# Main_board.net
KiCad netlist of a schematic drawn in EAGLE
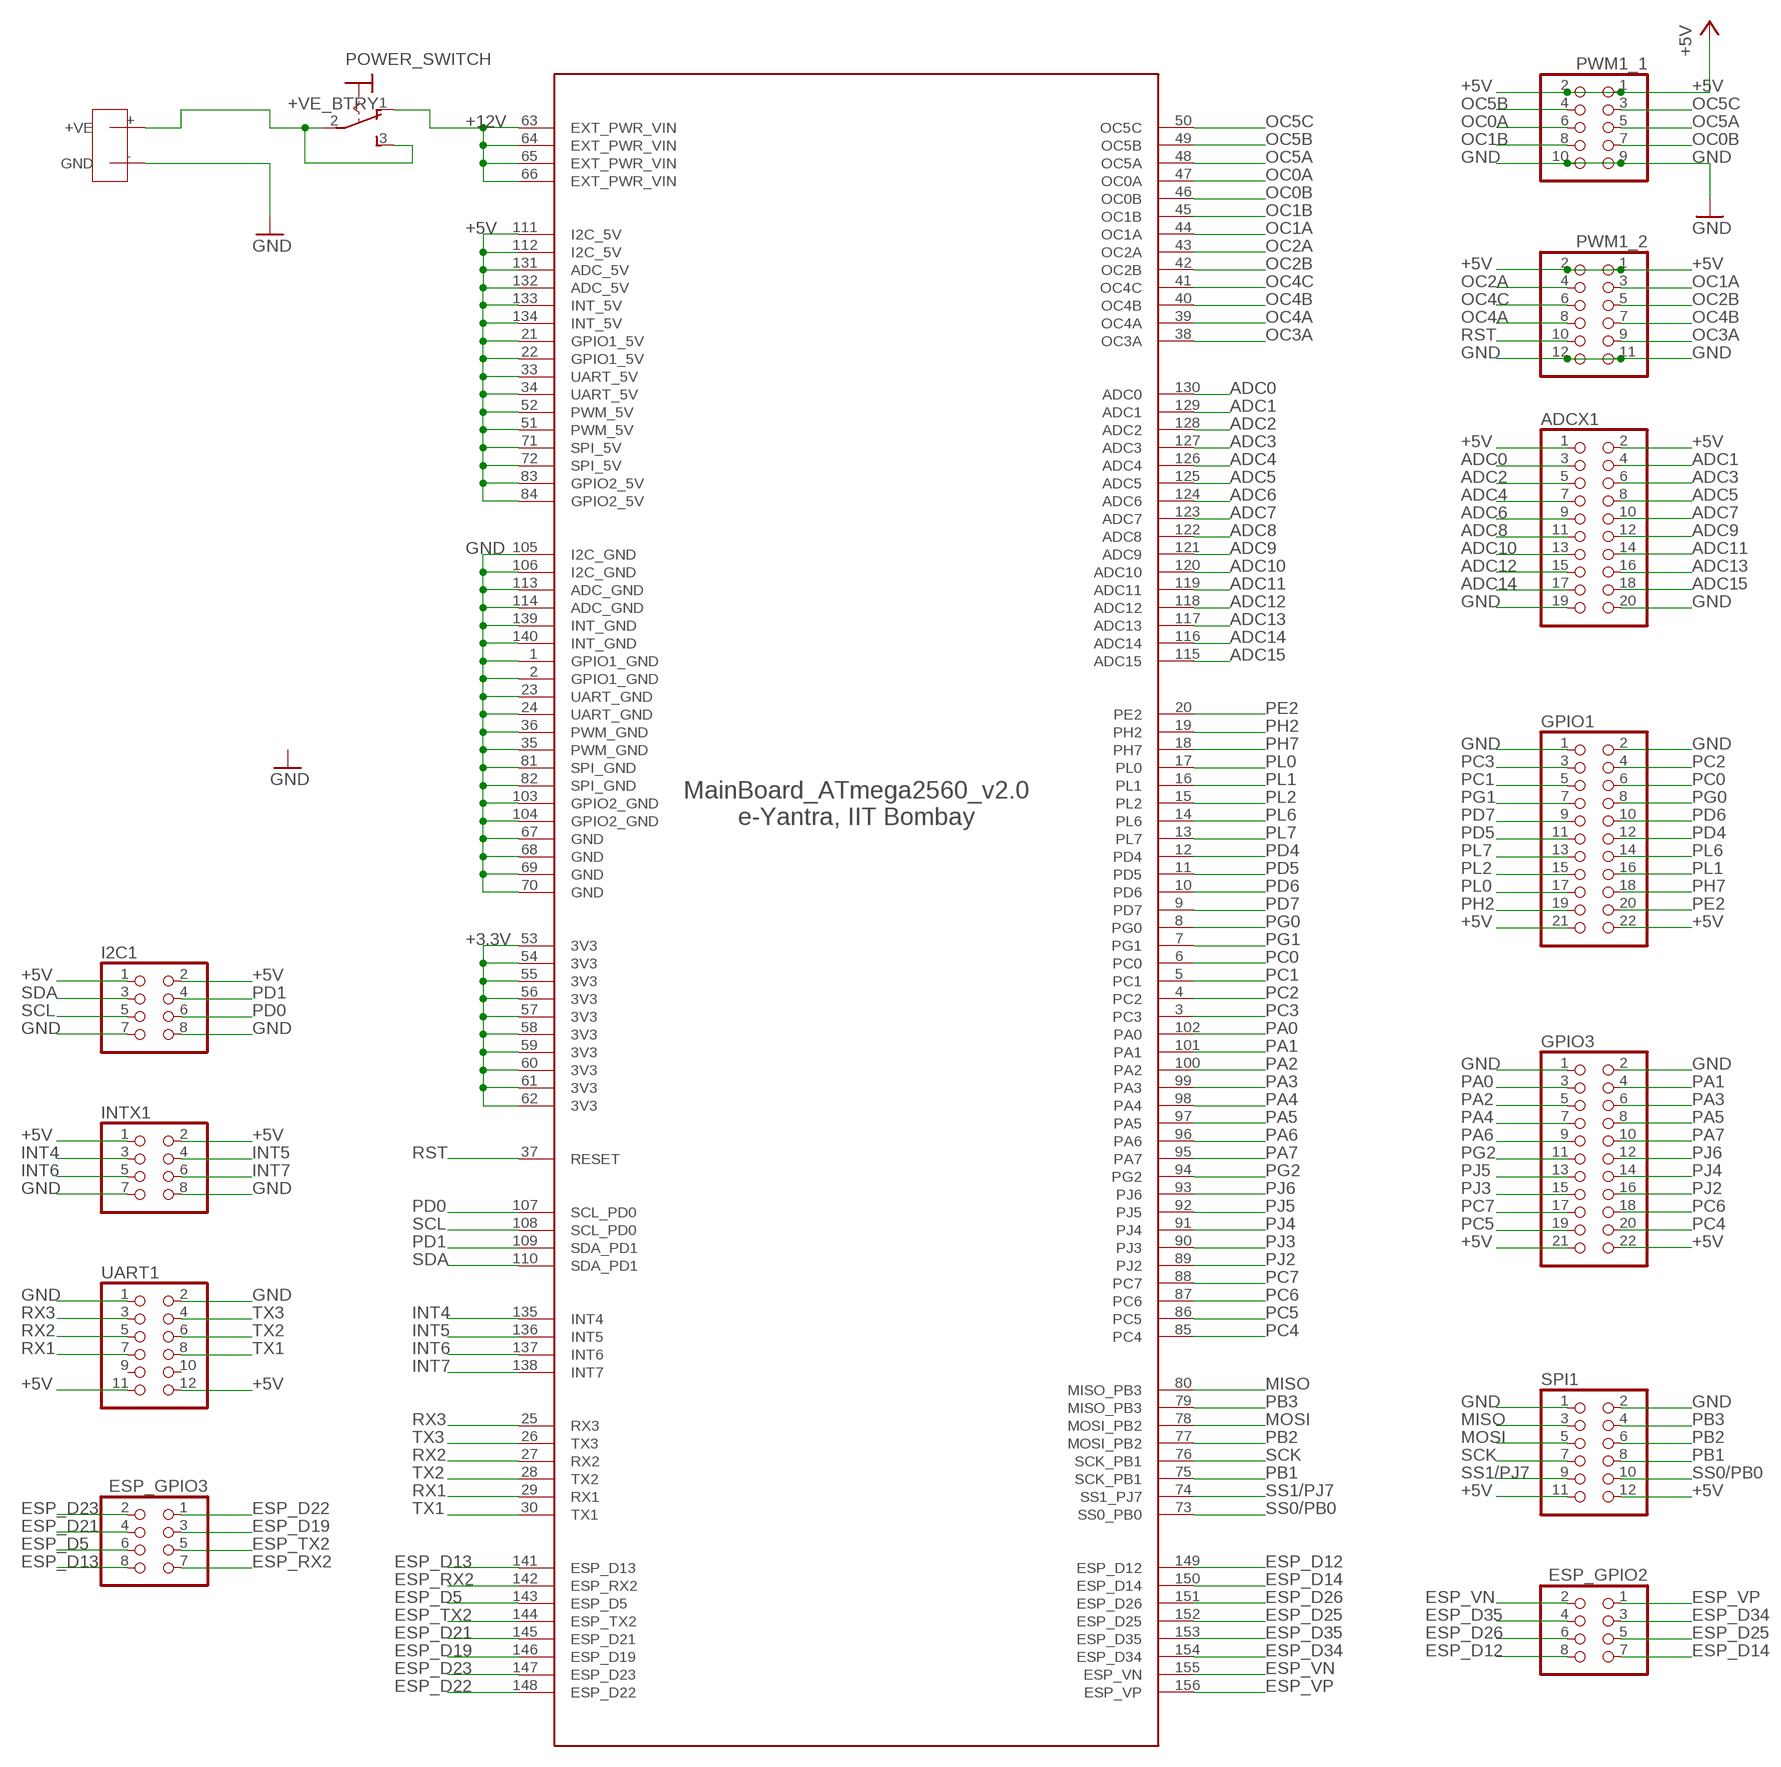
[diagram p0: schematic, sheet 1]
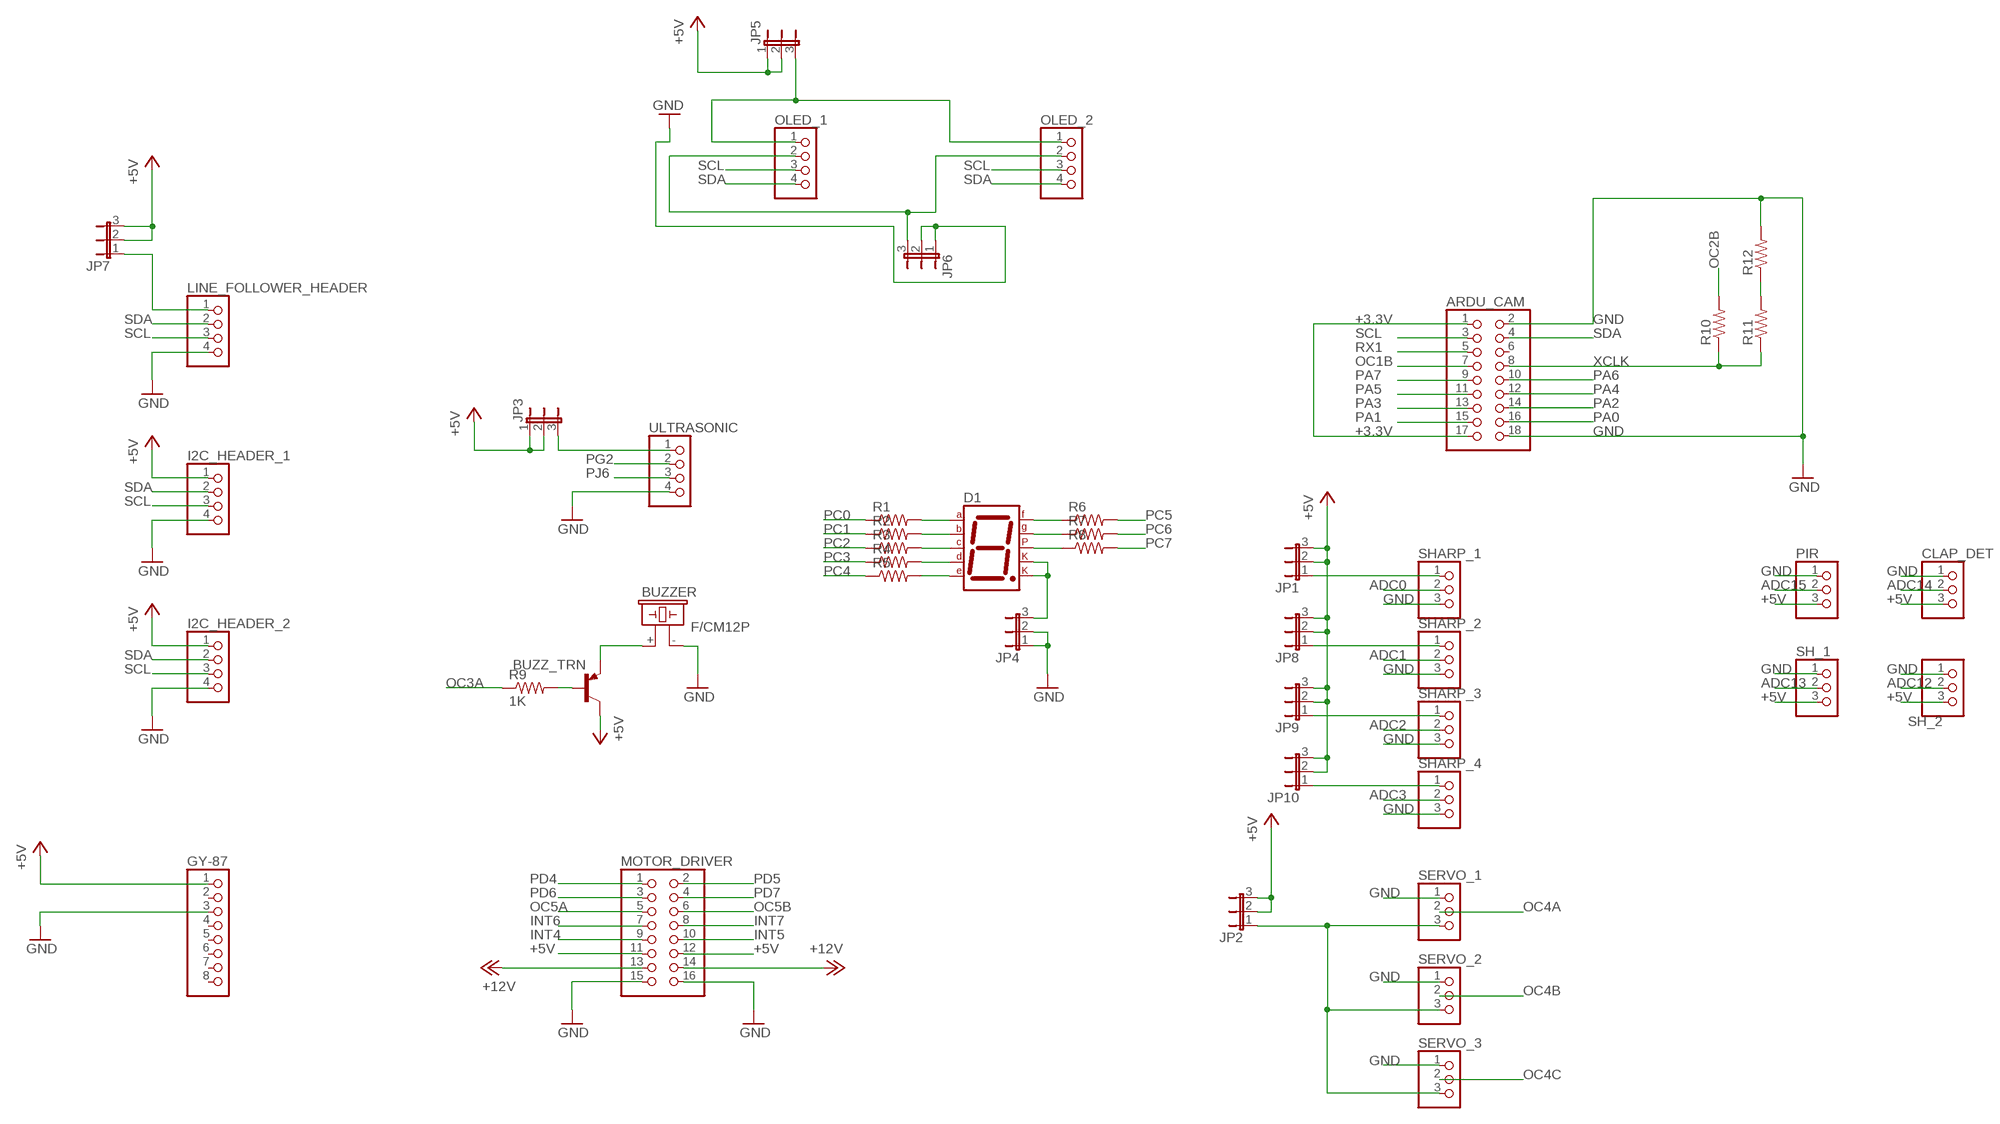
[diagram p1: schematic, sheet 2]

(export (version "E")
  (design (tool "Eeschema 10.0.6"))
  (components
    (comp (ref "ARDU_CAM")
      (value "PINHD-2X9")
      (footprint "eagle-import:2X09")
      (libsource (lib "eagle-import") (part "PINHD-2X9"))
    )
    (comp (ref "BUZZER")
      (value "F/CM12P")
      (footprint "eagle-import:F_CM12P")
      (libsource (lib "eagle-import") (part "F/CM12P"))
    )
    (comp (ref "BUZZ_TRN")
      (value "BC807-16-PNP-SOT23-BEC")
      (footprint "eagle-import:SOT23-BEC")
      (libsource (lib "eagle-import") (part "-PNP-SOT23-BECBC807-16"))
    )
    (comp (ref "CLAP_DET")
      (value "PINHD-1X3")
      (footprint "eagle-import:1X03")
      (libsource (lib "eagle-import") (part "pinhead_325_PINHD-1X3"))
    )
    (comp (ref "D1")
      (value "7SEG-CK")
      (footprint "eagle-import:7SEG-13")
      (libsource (lib "eagle-import") (part "7SEG-CK"))
    )
    (comp (ref "GY-87")
      (value "PINHD-1X8")
      (footprint "eagle-import:1X08")
      (libsource (lib "eagle-import") (part "PINHD-1X8"))
    )
    (comp (ref "I2C_HEADER_1")
      (value "PINHD-1X4")
      (footprint "eagle-import:1X04")
      (libsource (lib "eagle-import") (part "PINHD-1X4"))
    )
    (comp (ref "I2C_HEADER_2")
      (value "PINHD-1X4")
      (footprint "eagle-import:1X04")
      (libsource (lib "eagle-import") (part "PINHD-1X4"))
    )
    (comp (ref "JP1")
      (value "JP2E")
      (footprint "eagle-import:JP2")
      (libsource (lib "eagle-import") (part "JP2E"))
    )
    (comp (ref "JP2")
      (value "JP2E")
      (footprint "eagle-import:JP2")
      (libsource (lib "eagle-import") (part "JP2E"))
    )
    (comp (ref "JP3")
      (value "JP2E")
      (footprint "eagle-import:JP2")
      (libsource (lib "eagle-import") (part "JP2E"))
    )
    (comp (ref "JP4")
      (value "JP2E")
      (footprint "eagle-import:JP2")
      (libsource (lib "eagle-import") (part "JP2E"))
    )
    (comp (ref "JP5")
      (value "JP2E")
      (footprint "eagle-import:JP2")
      (libsource (lib "eagle-import") (part "JP2E"))
    )
    (comp (ref "JP6")
      (value "JP2E")
      (footprint "eagle-import:JP2")
      (libsource (lib "eagle-import") (part "JP2E"))
    )
    (comp (ref "JP7")
      (value "JP2E")
      (footprint "eagle-import:JP2")
      (libsource (lib "eagle-import") (part "JP2E"))
    )
    (comp (ref "JP8")
      (value "JP2E")
      (footprint "eagle-import:JP2")
      (libsource (lib "eagle-import") (part "JP2E"))
    )
    (comp (ref "JP9")
      (value "JP2E")
      (footprint "eagle-import:JP2")
      (libsource (lib "eagle-import") (part "JP2E"))
    )
    (comp (ref "JP10")
      (value "JP2E")
      (footprint "eagle-import:JP2")
      (libsource (lib "eagle-import") (part "JP2E"))
    )
    (comp (ref "LINE_FOLLOWER_HEADER")
      (value "PINHD-1X4")
      (footprint "eagle-import:1X04")
      (libsource (lib "eagle-import") (part "PINHD-1X4"))
    )
    (comp (ref "MOTOR_DRIVER")
      (value "PINHD-2X8")
      (footprint "eagle-import:2X08")
      (libsource (lib "eagle-import") (part "PINHD-2X8"))
    )
    (comp (ref "OLED_1")
      (value "PINHD-1X4")
      (footprint "eagle-import:1X04")
      (libsource (lib "eagle-import") (part "PINHD-1X4"))
    )
    (comp (ref "OLED_2")
      (value "PINHD-1X4")
      (footprint "eagle-import:1X04")
      (libsource (lib "eagle-import") (part "PINHD-1X4"))
    )
    (comp (ref "PIR")
      (value "PINHD-1X3")
      (footprint "eagle-import:1X03")
      (libsource (lib "eagle-import") (part "pinhead_325_PINHD-1X3"))
    )
    (comp (ref "R1")
      (value "R-US_R1206")
      (footprint "eagle-import:R1206")
      (libsource (lib "eagle-import") (part "R-US_R1206"))
    )
    (comp (ref "R2")
      (value "R-US_R1206")
      (footprint "eagle-import:R1206")
      (libsource (lib "eagle-import") (part "R-US_R1206"))
    )
    (comp (ref "R3")
      (value "R-US_R1206")
      (footprint "eagle-import:R1206")
      (libsource (lib "eagle-import") (part "R-US_R1206"))
    )
    (comp (ref "R4")
      (value "R-US_R1206")
      (footprint "eagle-import:R1206")
      (libsource (lib "eagle-import") (part "R-US_R1206"))
    )
    (comp (ref "R5")
      (value "R-US_R1206")
      (footprint "eagle-import:R1206")
      (libsource (lib "eagle-import") (part "R-US_R1206"))
    )
    (comp (ref "R6")
      (value "R-US_R1206")
      (footprint "eagle-import:R1206")
      (libsource (lib "eagle-import") (part "R-US_R1206"))
    )
    (comp (ref "R7")
      (value "R-US_R1206")
      (footprint "eagle-import:R1206")
      (libsource (lib "eagle-import") (part "R-US_R1206"))
    )
    (comp (ref "R8")
      (value "R-US_R1206")
      (footprint "eagle-import:R1206")
      (libsource (lib "eagle-import") (part "R-US_R1206"))
    )
    (comp (ref "R9")
      (value "1K")
      (footprint "eagle-import:R1206")
      (libsource (lib "eagle-import") (part "R-US_R1206"))
    )
    (comp (ref "R10")
      (value "R-US_R1206")
      (footprint "eagle-import:R1206")
      (libsource (lib "eagle-import") (part "R-US_R1206"))
    )
    (comp (ref "R11")
      (value "R-US_R1206")
      (footprint "eagle-import:R1206")
      (libsource (lib "eagle-import") (part "R-US_R1206"))
    )
    (comp (ref "R12")
      (value "R-US_R1206")
      (footprint "eagle-import:R1206")
      (libsource (lib "eagle-import") (part "R-US_R1206"))
    )
    (comp (ref "SERVO_1")
      (value "PINHD-1X3")
      (footprint "eagle-import:1X03")
      (libsource (lib "eagle-import") (part "pinhead_325_PINHD-1X3"))
    )
    (comp (ref "SERVO_2")
      (value "PINHD-1X3")
      (footprint "eagle-import:1X03")
      (libsource (lib "eagle-import") (part "pinhead_325_PINHD-1X3"))
    )
    (comp (ref "SERVO_3")
      (value "PINHD-1X3")
      (footprint "eagle-import:1X03")
      (libsource (lib "eagle-import") (part "pinhead_325_PINHD-1X3"))
    )
    (comp (ref "SHARP_1")
      (value "PINHD-1X3")
      (footprint "eagle-import:1X03")
      (libsource (lib "eagle-import") (part "PINHD-1X3"))
    )
    (comp (ref "SHARP_2")
      (value "PINHD-1X3")
      (footprint "eagle-import:1X03")
      (libsource (lib "eagle-import") (part "PINHD-1X3"))
    )
    (comp (ref "SHARP_3")
      (value "PINHD-1X3")
      (footprint "eagle-import:1X03")
      (libsource (lib "eagle-import") (part "PINHD-1X3"))
    )
    (comp (ref "SHARP_4")
      (value "PINHD-1X3")
      (footprint "eagle-import:1X03")
      (libsource (lib "eagle-import") (part "PINHD-1X3"))
    )
    (comp (ref "SH_1")
      (value "PINHD-1X3")
      (footprint "eagle-import:1X03")
      (libsource (lib "eagle-import") (part "pinhead_325_PINHD-1X3"))
    )
    (comp (ref "SH_2")
      (value "PINHD-1X3")
      (footprint "eagle-import:1X03")
      (libsource (lib "eagle-import") (part "pinhead_325_PINHD-1X3"))
    )
    (comp (ref "ULTRASONIC")
      (value "PINHD-1X4")
      (footprint "eagle-import:1X04")
      (libsource (lib "eagle-import") (part "PINHD-1X4"))
    )
    (comp (ref "ADCX1")
      (value "PINHD-2X10")
      (footprint "eagle-import:2X10")
      (libsource (lib "eagle-import") (part "PINHD-2X10"))
    )
    (comp (ref "ESP_GPIO2")
      (value "PINHD-2X4")
      (footprint "eagle-import:2X04")
      (libsource (lib "eagle-import") (part "PINHD-2X4"))
    )
    (comp (ref "ESP_GPIO3")
      (value "PINHD-2X4")
      (footprint "eagle-import:2X04")
      (libsource (lib "eagle-import") (part "PINHD-2X4"))
    )
    (comp (ref "EYFI_MEGA")
      (value "ATMEGA2560_V2.0")
      (footprint "eagle-import:ATMEGA2560_V2.0")
      (libsource (lib "eagle-import") (part "ATMEGA2560_V2.0"))
    )
    (comp (ref "GPIO1")
      (value "PINHD-2X11")
      (footprint "eagle-import:2X11")
      (libsource (lib "eagle-import") (part "PINHD-2X11"))
    )
    (comp (ref "GPIO3")
      (value "PINHD-2X11")
      (footprint "eagle-import:2X11")
      (libsource (lib "eagle-import") (part "PINHD-2X11"))
    )
    (comp (ref "I2C1")
      (value "PINHD-2X4")
      (footprint "eagle-import:2X04")
      (libsource (lib "eagle-import") (part "PINHD-2X4"))
    )
    (comp (ref "INTX1")
      (value "PINHD-2X4")
      (footprint "eagle-import:2X04")
      (libsource (lib "eagle-import") (part "PINHD-2X4"))
    )
    (comp (ref "POWER_SWITCH")
      (value "M9040P")
      (footprint "eagle-import:M9040P")
      (libsource (lib "eagle-import") (part "M9040P"))
    )
    (comp (ref "PWM1_1")
      (value "PINHD-2X5")
      (footprint "eagle-import:2X05")
      (libsource (lib "eagle-import") (part "PINHD-2X5"))
    )
    (comp (ref "PWM1_2")
      (value "PINHD-2X6")
      (footprint "eagle-import:2X06")
      (libsource (lib "eagle-import") (part "PINHD-2X6"))
    )
    (comp (ref "SPI1")
      (value "PINHD-2X6")
      (footprint "eagle-import:2X06")
      (libsource (lib "eagle-import") (part "PINHD-2X6"))
    )
    (comp (ref "U$1")
      (value "DEANS")
      (footprint "eagle-import:DEANS")
      (libsource (lib "eagle-import") (part "DEANS"))
    )
    (comp (ref "UART1")
      (value "PINHD-2X6")
      (footprint "eagle-import:2X06")
      (libsource (lib "eagle-import") (part "PINHD-2X6"))
    )
  )
  (nets
    (net (code "1") (name "+3.3V") (class "Default")
      (node (ref "ARDU_CAM") (pin "1") (pinfunction "1_1") (pintype "passive"))
      (node (ref "ARDU_CAM") (pin "17") (pinfunction "17_17") (pintype "passive"))
      (node (ref "EYFI_MEGA") (pin "53") (pinfunction "3V3_53") (pintype "power_in"))
      (node (ref "EYFI_MEGA") (pin "54") (pinfunction "3V3_54") (pintype "power_in"))
      (node (ref "EYFI_MEGA") (pin "55") (pinfunction "3V3_55") (pintype "power_in"))
      (node (ref "EYFI_MEGA") (pin "56") (pinfunction "3V3_56") (pintype "power_in"))
      (node (ref "EYFI_MEGA") (pin "57") (pinfunction "3V3_57") (pintype "power_in"))
      (node (ref "EYFI_MEGA") (pin "58") (pinfunction "3V3_58") (pintype "power_in"))
      (node (ref "EYFI_MEGA") (pin "59") (pinfunction "3V3_59") (pintype "power_in"))
      (node (ref "EYFI_MEGA") (pin "60") (pinfunction "3V3_60") (pintype "power_in"))
      (node (ref "EYFI_MEGA") (pin "61") (pinfunction "3V3_61") (pintype "power_in"))
      (node (ref "EYFI_MEGA") (pin "62") (pinfunction "3V3_62") (pintype "power_in"))
    )
    (net (code "2") (name "+5V") (class "Default")
      (node (ref "ADCX1") (pin "1") (pinfunction "1_1") (pintype "passive"))
      (node (ref "ADCX1") (pin "2") (pinfunction "2_2") (pintype "passive"))
      (node (ref "BUZZ_TRN") (pin "C") (pinfunction "C_C") (pintype "passive"))
      (node (ref "CLAP_DET") (pin "3") (pinfunction "3_3") (pintype "passive"))
      (node (ref "EYFI_MEGA") (pin "111") (pinfunction "I2C_5V_111") (pintype "power_in"))
      (node (ref "EYFI_MEGA") (pin "112") (pinfunction "I2C_5V_112") (pintype "power_in"))
      (node (ref "EYFI_MEGA") (pin "131") (pinfunction "ADC_5V_131") (pintype "power_in"))
      (node (ref "EYFI_MEGA") (pin "132") (pinfunction "ADC_5V_132") (pintype "power_in"))
      (node (ref "EYFI_MEGA") (pin "133") (pinfunction "INT_5V_133") (pintype "power_in"))
      (node (ref "EYFI_MEGA") (pin "134") (pinfunction "INT_5V_134") (pintype "power_in"))
      (node (ref "EYFI_MEGA") (pin "21") (pinfunction "GPIO1_5V_21") (pintype "power_in"))
      (node (ref "EYFI_MEGA") (pin "22") (pinfunction "GPIO1_5V_22") (pintype "power_in"))
      (node (ref "EYFI_MEGA") (pin "33") (pinfunction "UART_5V_33") (pintype "power_in"))
      (node (ref "EYFI_MEGA") (pin "34") (pinfunction "UART_5V_34") (pintype "power_in"))
      (node (ref "EYFI_MEGA") (pin "51") (pinfunction "PWM_5V_51") (pintype "power_in"))
      (node (ref "EYFI_MEGA") (pin "52") (pinfunction "PWM_5V_52") (pintype "power_in"))
      (node (ref "EYFI_MEGA") (pin "71") (pinfunction "SPI_5V_71") (pintype "power_in"))
      (node (ref "EYFI_MEGA") (pin "72") (pinfunction "SPI_5V_72") (pintype "power_in"))
      (node (ref "EYFI_MEGA") (pin "83") (pinfunction "GPIO2_5V_83") (pintype "power_in"))
      (node (ref "EYFI_MEGA") (pin "84") (pinfunction "GPIO2_5V_84") (pintype "power_in"))
      (node (ref "GPIO1") (pin "21") (pinfunction "21_21") (pintype "passive"))
      (node (ref "GPIO1") (pin "22") (pinfunction "22_22") (pintype "passive"))
      (node (ref "GPIO3") (pin "21") (pinfunction "21_21") (pintype "passive"))
      (node (ref "GPIO3") (pin "22") (pinfunction "22_22") (pintype "passive"))
      (node (ref "GY-87") (pin "1") (pinfunction "1_1") (pintype "passive"))
      (node (ref "I2C1") (pin "1") (pinfunction "1_1") (pintype "passive"))
      (node (ref "I2C1") (pin "2") (pinfunction "2_2") (pintype "passive"))
      (node (ref "I2C_HEADER_1") (pin "1") (pinfunction "1_1") (pintype "passive"))
      (node (ref "I2C_HEADER_2") (pin "1") (pinfunction "1_1") (pintype "passive"))
      (node (ref "INTX1") (pin "1") (pinfunction "1_1") (pintype "passive"))
      (node (ref "INTX1") (pin "2") (pinfunction "2_2") (pintype "passive"))
      (node (ref "JP1") (pin "2") (pinfunction "2_2") (pintype "passive"))
      (node (ref "JP1") (pin "3") (pinfunction "3_3") (pintype "passive"))
      (node (ref "JP10") (pin "2") (pinfunction "2_2") (pintype "passive"))
      (node (ref "JP10") (pin "3") (pinfunction "3_3") (pintype "passive"))
      (node (ref "JP2") (pin "2") (pinfunction "2_2") (pintype "passive"))
      (node (ref "JP2") (pin "3") (pinfunction "3_3") (pintype "passive"))
      (node (ref "JP3") (pin "1") (pinfunction "1_1") (pintype "passive"))
      (node (ref "JP3") (pin "2") (pinfunction "2_2") (pintype "passive"))
      (node (ref "JP5") (pin "1") (pinfunction "1_1") (pintype "passive"))
      (node (ref "JP5") (pin "2") (pinfunction "2_2") (pintype "passive"))
      (node (ref "JP7") (pin "2") (pinfunction "2_2") (pintype "passive"))
      (node (ref "JP7") (pin "3") (pinfunction "3_3") (pintype "passive"))
      (node (ref "JP8") (pin "2") (pinfunction "2_2") (pintype "passive"))
      (node (ref "JP8") (pin "3") (pinfunction "3_3") (pintype "passive"))
      (node (ref "JP9") (pin "2") (pinfunction "2_2") (pintype "passive"))
      (node (ref "JP9") (pin "3") (pinfunction "3_3") (pintype "passive"))
      (node (ref "MOTOR_DRIVER") (pin "11") (pinfunction "11_11") (pintype "passive"))
      (node (ref "MOTOR_DRIVER") (pin "12") (pinfunction "12_12") (pintype "passive"))
      (node (ref "PIR") (pin "3") (pinfunction "3_3") (pintype "passive"))
      (node (ref "PWM1_1") (pin "1") (pinfunction "1_1") (pintype "passive"))
      (node (ref "PWM1_1") (pin "2") (pinfunction "2_2") (pintype "passive"))
      (node (ref "PWM1_2") (pin "1") (pinfunction "1_1") (pintype "passive"))
      (node (ref "PWM1_2") (pin "2") (pinfunction "2_2") (pintype "passive"))
      (node (ref "SH_1") (pin "3") (pinfunction "3_3") (pintype "passive"))
      (node (ref "SH_2") (pin "3") (pinfunction "3_3") (pintype "passive"))
      (node (ref "SPI1") (pin "11") (pinfunction "11_11") (pintype "passive"))
      (node (ref "SPI1") (pin "12") (pinfunction "12_12") (pintype "passive"))
      (node (ref "UART1") (pin "11") (pinfunction "11_11") (pintype "passive"))
      (node (ref "UART1") (pin "12") (pinfunction "12_12") (pintype "passive"))
    )
    (net (code "3") (name "+12V") (class "Default")
      (node (ref "EYFI_MEGA") (pin "63") (pinfunction "EXT_PWR_VIN_63") (pintype "power_in"))
      (node (ref "EYFI_MEGA") (pin "64") (pinfunction "EXT_PWR_VIN_64") (pintype "power_in"))
      (node (ref "EYFI_MEGA") (pin "65") (pinfunction "EXT_PWR_VIN_65") (pintype "power_in"))
      (node (ref "EYFI_MEGA") (pin "66") (pinfunction "EXT_PWR_VIN_66") (pintype "power_in"))
      (node (ref "MOTOR_DRIVER") (pin "13") (pinfunction "13_13") (pintype "passive"))
      (node (ref "MOTOR_DRIVER") (pin "14") (pinfunction "14_14") (pintype "passive"))
      (node (ref "POWER_SWITCH") (pin "1") (pinfunction "O_1") (pintype "passive"))
    )
    (net (code "4") (name "+VE_BTRY") (class "Default")
      (node (ref "POWER_SWITCH") (pin "2") (pinfunction "P_2") (pintype "passive"))
      (node (ref "POWER_SWITCH") (pin "3") (pinfunction "S_3") (pintype "passive"))
      (node (ref "U$1") (pin "+") (pinfunction "+VE_+") (pintype "bidirectional"))
    )
    (net (code "5") (name "ADC0") (class "Default")
      (node (ref "ADCX1") (pin "3") (pinfunction "3_3") (pintype "passive"))
      (node (ref "EYFI_MEGA") (pin "130") (pinfunction "ADC0_130") (pintype "bidirectional"))
      (node (ref "SHARP_1") (pin "2") (pinfunction "2_2") (pintype "passive"))
    )
    (net (code "6") (name "ADC1") (class "Default")
      (node (ref "ADCX1") (pin "4") (pinfunction "4_4") (pintype "passive"))
      (node (ref "EYFI_MEGA") (pin "129") (pinfunction "ADC1_129") (pintype "bidirectional"))
      (node (ref "SHARP_2") (pin "2") (pinfunction "2_2") (pintype "passive"))
    )
    (net (code "7") (name "ADC2") (class "Default")
      (node (ref "ADCX1") (pin "5") (pinfunction "5_5") (pintype "passive"))
      (node (ref "EYFI_MEGA") (pin "128") (pinfunction "ADC2_128") (pintype "bidirectional"))
      (node (ref "SHARP_3") (pin "2") (pinfunction "2_2") (pintype "passive"))
    )
    (net (code "8") (name "ADC3") (class "Default")
      (node (ref "ADCX1") (pin "6") (pinfunction "6_6") (pintype "passive"))
      (node (ref "EYFI_MEGA") (pin "127") (pinfunction "ADC3_127") (pintype "bidirectional"))
      (node (ref "SHARP_4") (pin "2") (pinfunction "2_2") (pintype "passive"))
    )
    (net (code "9") (name "ADC4") (class "Default")
      (node (ref "ADCX1") (pin "7") (pinfunction "7_7") (pintype "passive"))
      (node (ref "EYFI_MEGA") (pin "126") (pinfunction "ADC4_126") (pintype "bidirectional"))
    )
    (net (code "10") (name "ADC5") (class "Default")
      (node (ref "ADCX1") (pin "8") (pinfunction "8_8") (pintype "passive"))
      (node (ref "EYFI_MEGA") (pin "125") (pinfunction "ADC5_125") (pintype "bidirectional"))
    )
    (net (code "11") (name "ADC6") (class "Default")
      (node (ref "ADCX1") (pin "9") (pinfunction "9_9") (pintype "passive"))
      (node (ref "EYFI_MEGA") (pin "124") (pinfunction "ADC6_124") (pintype "bidirectional"))
    )
    (net (code "12") (name "ADC7") (class "Default")
      (node (ref "ADCX1") (pin "10") (pinfunction "10_10") (pintype "passive"))
      (node (ref "EYFI_MEGA") (pin "123") (pinfunction "ADC7_123") (pintype "bidirectional"))
    )
    (net (code "13") (name "ADC8") (class "Default")
      (node (ref "ADCX1") (pin "11") (pinfunction "11_11") (pintype "passive"))
      (node (ref "EYFI_MEGA") (pin "122") (pinfunction "ADC8_122") (pintype "bidirectional"))
    )
    (net (code "14") (name "ADC9") (class "Default")
      (node (ref "ADCX1") (pin "12") (pinfunction "12_12") (pintype "passive"))
      (node (ref "EYFI_MEGA") (pin "121") (pinfunction "ADC9_121") (pintype "bidirectional"))
    )
    (net (code "15") (name "ADC10") (class "Default")
      (node (ref "ADCX1") (pin "13") (pinfunction "13_13") (pintype "passive"))
      (node (ref "EYFI_MEGA") (pin "120") (pinfunction "ADC10_120") (pintype "bidirectional"))
    )
    (net (code "16") (name "ADC11") (class "Default")
      (node (ref "ADCX1") (pin "14") (pinfunction "14_14") (pintype "passive"))
      (node (ref "EYFI_MEGA") (pin "119") (pinfunction "ADC11_119") (pintype "bidirectional"))
    )
    (net (code "17") (name "ADC12") (class "Default")
      (node (ref "ADCX1") (pin "15") (pinfunction "15_15") (pintype "passive"))
      (node (ref "EYFI_MEGA") (pin "118") (pinfunction "ADC12_118") (pintype "bidirectional"))
      (node (ref "SH_2") (pin "2") (pinfunction "2_2") (pintype "passive"))
    )
    (net (code "18") (name "ADC13") (class "Default")
      (node (ref "ADCX1") (pin "16") (pinfunction "16_16") (pintype "passive"))
      (node (ref "EYFI_MEGA") (pin "117") (pinfunction "ADC13_117") (pintype "bidirectional"))
      (node (ref "SH_1") (pin "2") (pinfunction "2_2") (pintype "passive"))
    )
    (net (code "19") (name "ADC14") (class "Default")
      (node (ref "ADCX1") (pin "17") (pinfunction "17_17") (pintype "passive"))
      (node (ref "CLAP_DET") (pin "2") (pinfunction "2_2") (pintype "passive"))
      (node (ref "EYFI_MEGA") (pin "116") (pinfunction "ADC14_116") (pintype "bidirectional"))
    )
    (net (code "20") (name "ADC15") (class "Default")
      (node (ref "ADCX1") (pin "18") (pinfunction "18_18") (pintype "passive"))
      (node (ref "EYFI_MEGA") (pin "115") (pinfunction "ADC15_115") (pintype "bidirectional"))
      (node (ref "PIR") (pin "2") (pinfunction "2_2") (pintype "passive"))
    )
    (net (code "21") (name "ESP_D5") (class "Default")
      (node (ref "ESP_GPIO3") (pin "6") (pinfunction "6_6") (pintype "passive"))
      (node (ref "EYFI_MEGA") (pin "143") (pinfunction "ESP_D5_143") (pintype "bidirectional"))
    )
    (net (code "22") (name "ESP_D12") (class "Default")
      (node (ref "ESP_GPIO2") (pin "8") (pinfunction "8_8") (pintype "passive"))
      (node (ref "EYFI_MEGA") (pin "149") (pinfunction "ESP_D12_149") (pintype "bidirectional"))
    )
    (net (code "23") (name "ESP_D13") (class "Default")
      (node (ref "ESP_GPIO3") (pin "8") (pinfunction "8_8") (pintype "passive"))
      (node (ref "EYFI_MEGA") (pin "141") (pinfunction "ESP_D13_141") (pintype "bidirectional"))
    )
    (net (code "24") (name "ESP_D14") (class "Default")
      (node (ref "ESP_GPIO2") (pin "7") (pinfunction "7_7") (pintype "passive"))
      (node (ref "EYFI_MEGA") (pin "150") (pinfunction "ESP_D14_150") (pintype "bidirectional"))
    )
    (net (code "25") (name "ESP_D19") (class "Default")
      (node (ref "ESP_GPIO3") (pin "3") (pinfunction "3_3") (pintype "passive"))
      (node (ref "EYFI_MEGA") (pin "146") (pinfunction "ESP_D19_146") (pintype "bidirectional"))
    )
    (net (code "26") (name "ESP_D21") (class "Default")
      (node (ref "ESP_GPIO3") (pin "4") (pinfunction "4_4") (pintype "passive"))
      (node (ref "EYFI_MEGA") (pin "145") (pinfunction "ESP_D21_145") (pintype "bidirectional"))
    )
    (net (code "27") (name "ESP_D22") (class "Default")
      (node (ref "ESP_GPIO3") (pin "1") (pinfunction "1_1") (pintype "passive"))
      (node (ref "EYFI_MEGA") (pin "148") (pinfunction "ESP_D22_148") (pintype "bidirectional"))
    )
    (net (code "28") (name "ESP_D23") (class "Default")
      (node (ref "ESP_GPIO3") (pin "2") (pinfunction "2_2") (pintype "passive"))
      (node (ref "EYFI_MEGA") (pin "147") (pinfunction "ESP_D23_147") (pintype "bidirectional"))
    )
    (net (code "29") (name "ESP_D25") (class "Default")
      (node (ref "ESP_GPIO2") (pin "5") (pinfunction "5_5") (pintype "passive"))
      (node (ref "EYFI_MEGA") (pin "152") (pinfunction "ESP_D25_152") (pintype "bidirectional"))
    )
    (net (code "30") (name "ESP_D26") (class "Default")
      (node (ref "ESP_GPIO2") (pin "6") (pinfunction "6_6") (pintype "passive"))
      (node (ref "EYFI_MEGA") (pin "151") (pinfunction "ESP_D26_151") (pintype "bidirectional"))
    )
    (net (code "31") (name "ESP_D34") (class "Default")
      (node (ref "ESP_GPIO2") (pin "3") (pinfunction "3_3") (pintype "passive"))
      (node (ref "EYFI_MEGA") (pin "154") (pinfunction "ESP_D34_154") (pintype "bidirectional"))
    )
    (net (code "32") (name "ESP_D35") (class "Default")
      (node (ref "ESP_GPIO2") (pin "4") (pinfunction "4_4") (pintype "passive"))
      (node (ref "EYFI_MEGA") (pin "153") (pinfunction "ESP_D35_153") (pintype "bidirectional"))
    )
    (net (code "33") (name "ESP_RX2") (class "Default")
      (node (ref "ESP_GPIO3") (pin "7") (pinfunction "7_7") (pintype "passive"))
      (node (ref "EYFI_MEGA") (pin "142") (pinfunction "ESP_RX2_142") (pintype "bidirectional"))
    )
    (net (code "34") (name "ESP_TX2") (class "Default")
      (node (ref "ESP_GPIO3") (pin "5") (pinfunction "5_5") (pintype "passive"))
      (node (ref "EYFI_MEGA") (pin "144") (pinfunction "ESP_TX2_144") (pintype "bidirectional"))
    )
    (net (code "35") (name "ESP_VN") (class "Default")
      (node (ref "ESP_GPIO2") (pin "2") (pinfunction "2_2") (pintype "passive"))
      (node (ref "EYFI_MEGA") (pin "155") (pinfunction "ESP_VN_155") (pintype "bidirectional"))
    )
    (net (code "36") (name "ESP_VP") (class "Default")
      (node (ref "ESP_GPIO2") (pin "1") (pinfunction "1_1") (pintype "passive"))
      (node (ref "EYFI_MEGA") (pin "156") (pinfunction "ESP_VP_156") (pintype "bidirectional"))
    )
    (net (code "37") (name "GND") (class "Default")
      (node (ref "ADCX1") (pin "19") (pinfunction "19_19") (pintype "passive"))
      (node (ref "ADCX1") (pin "20") (pinfunction "20_20") (pintype "passive"))
      (node (ref "ARDU_CAM") (pin "18") (pinfunction "18_18") (pintype "passive"))
      (node (ref "ARDU_CAM") (pin "2") (pinfunction "2_2") (pintype "passive"))
      (node (ref "BUZZER") (pin "-") (pinfunction "2_-") (pintype "passive"))
      (node (ref "CLAP_DET") (pin "1") (pinfunction "1_1") (pintype "passive"))
      (node (ref "EYFI_MEGA") (pin "1") (pinfunction "GPIO1_GND_1") (pintype "power_in"))
      (node (ref "EYFI_MEGA") (pin "103") (pinfunction "GPIO2_GND_103") (pintype "power_in"))
      (node (ref "EYFI_MEGA") (pin "104") (pinfunction "GPIO2_GND_104") (pintype "power_in"))
      (node (ref "EYFI_MEGA") (pin "105") (pinfunction "I2C_GND_105") (pintype "power_in"))
      (node (ref "EYFI_MEGA") (pin "106") (pinfunction "I2C_GND_106") (pintype "power_in"))
      (node (ref "EYFI_MEGA") (pin "113") (pinfunction "ADC_GND_113") (pintype "power_in"))
      (node (ref "EYFI_MEGA") (pin "114") (pinfunction "ADC_GND_114") (pintype "power_in"))
      (node (ref "EYFI_MEGA") (pin "139") (pinfunction "INT_GND_139") (pintype "power_in"))
      (node (ref "EYFI_MEGA") (pin "140") (pinfunction "INT_GND_140") (pintype "power_in"))
      (node (ref "EYFI_MEGA") (pin "2") (pinfunction "GPIO1_GND_2") (pintype "power_in"))
      (node (ref "EYFI_MEGA") (pin "23") (pinfunction "UART_GND_23") (pintype "power_in"))
      (node (ref "EYFI_MEGA") (pin "24") (pinfunction "UART_GND_24") (pintype "power_in"))
      (node (ref "EYFI_MEGA") (pin "35") (pinfunction "PWM_GND_35") (pintype "power_in"))
      (node (ref "EYFI_MEGA") (pin "36") (pinfunction "PWM_GND_36") (pintype "power_in"))
      (node (ref "EYFI_MEGA") (pin "67") (pinfunction "GND_67") (pintype "power_in"))
      (node (ref "EYFI_MEGA") (pin "68") (pinfunction "GND_68") (pintype "power_in"))
      (node (ref "EYFI_MEGA") (pin "69") (pinfunction "GND_69") (pintype "power_in"))
      (node (ref "EYFI_MEGA") (pin "70") (pinfunction "GND_70") (pintype "power_in"))
      (node (ref "EYFI_MEGA") (pin "81") (pinfunction "SPI_GND_81") (pintype "power_in"))
      (node (ref "EYFI_MEGA") (pin "82") (pinfunction "SPI_GND_82") (pintype "power_in"))
      (node (ref "GPIO1") (pin "1") (pinfunction "1_1") (pintype "passive"))
      (node (ref "GPIO1") (pin "2") (pinfunction "2_2") (pintype "passive"))
      (node (ref "GPIO3") (pin "1") (pinfunction "1_1") (pintype "passive"))
      (node (ref "GPIO3") (pin "2") (pinfunction "2_2") (pintype "passive"))
      (node (ref "GY-87") (pin "3") (pinfunction "3_3") (pintype "passive"))
      (node (ref "I2C1") (pin "7") (pinfunction "7_7") (pintype "passive"))
      (node (ref "I2C1") (pin "8") (pinfunction "8_8") (pintype "passive"))
      (node (ref "I2C_HEADER_1") (pin "4") (pinfunction "4_4") (pintype "passive"))
      (node (ref "I2C_HEADER_2") (pin "4") (pinfunction "4_4") (pintype "passive"))
      (node (ref "INTX1") (pin "7") (pinfunction "7_7") (pintype "passive"))
      (node (ref "INTX1") (pin "8") (pinfunction "8_8") (pintype "passive"))
      (node (ref "JP4") (pin "1") (pinfunction "1_1") (pintype "passive"))
      (node (ref "JP4") (pin "2") (pinfunction "2_2") (pintype "passive"))
      (node (ref "JP6") (pin "1") (pinfunction "1_1") (pintype "passive"))
      (node (ref "JP6") (pin "2") (pinfunction "2_2") (pintype "passive"))
      (node (ref "LINE_FOLLOWER_HEADER") (pin "4") (pinfunction "4_4") (pintype "passive"))
      (node (ref "MOTOR_DRIVER") (pin "15") (pinfunction "15_15") (pintype "passive"))
      (node (ref "MOTOR_DRIVER") (pin "16") (pinfunction "16_16") (pintype "passive"))
      (node (ref "PIR") (pin "1") (pinfunction "1_1") (pintype "passive"))
      (node (ref "PWM1_1") (pin "10") (pinfunction "10_10") (pintype "passive"))
      (node (ref "PWM1_1") (pin "9") (pinfunction "9_9") (pintype "passive"))
      (node (ref "PWM1_2") (pin "11") (pinfunction "11_11") (pintype "passive"))
      (node (ref "PWM1_2") (pin "12") (pinfunction "12_12") (pintype "passive"))
      (node (ref "R12") (pin "2") (pinfunction "2_2") (pintype "passive"))
      (node (ref "SERVO_1") (pin "1") (pinfunction "1_1") (pintype "passive"))
      (node (ref "SERVO_2") (pin "1") (pinfunction "1_1") (pintype "passive"))
      (node (ref "SERVO_3") (pin "1") (pinfunction "1_1") (pintype "passive"))
      (node (ref "SHARP_1") (pin "3") (pinfunction "3_3") (pintype "passive"))
      (node (ref "SHARP_2") (pin "3") (pinfunction "3_3") (pintype "passive"))
      (node (ref "SHARP_3") (pin "3") (pinfunction "3_3") (pintype "passive"))
      (node (ref "SHARP_4") (pin "3") (pinfunction "3_3") (pintype "passive"))
      (node (ref "SH_1") (pin "1") (pinfunction "1_1") (pintype "passive"))
      (node (ref "SH_2") (pin "1") (pinfunction "1_1") (pintype "passive"))
      (node (ref "SPI1") (pin "1") (pinfunction "1_1") (pintype "passive"))
      (node (ref "SPI1") (pin "2") (pinfunction "2_2") (pintype "passive"))
      (node (ref "U$1") (pin "-") (pinfunction "GND_-") (pintype "bidirectional"))
      (node (ref "UART1") (pin "1") (pinfunction "1_1") (pintype "passive"))
      (node (ref "UART1") (pin "2") (pinfunction "2_2") (pintype "passive"))
      (node (ref "ULTRASONIC") (pin "4") (pinfunction "4_4") (pintype "passive"))
    )
    (net (code "38") (name "INT4") (class "Default")
      (node (ref "EYFI_MEGA") (pin "135") (pinfunction "INT4_135") (pintype "bidirectional"))
      (node (ref "INTX1") (pin "3") (pinfunction "3_3") (pintype "passive"))
      (node (ref "MOTOR_DRIVER") (pin "9") (pinfunction "9_9") (pintype "passive"))
    )
    (net (code "39") (name "INT5") (class "Default")
      (node (ref "EYFI_MEGA") (pin "136") (pinfunction "INT5_136") (pintype "bidirectional"))
      (node (ref "INTX1") (pin "4") (pinfunction "4_4") (pintype "passive"))
      (node (ref "MOTOR_DRIVER") (pin "10") (pinfunction "10_10") (pintype "passive"))
    )
    (net (code "40") (name "INT6") (class "Default")
      (node (ref "EYFI_MEGA") (pin "137") (pinfunction "INT6_137") (pintype "bidirectional"))
      (node (ref "INTX1") (pin "5") (pinfunction "5_5") (pintype "passive"))
      (node (ref "MOTOR_DRIVER") (pin "7") (pinfunction "7_7") (pintype "passive"))
    )
    (net (code "41") (name "INT7") (class "Default")
      (node (ref "EYFI_MEGA") (pin "138") (pinfunction "INT7_138") (pintype "bidirectional"))
      (node (ref "INTX1") (pin "6") (pinfunction "6_6") (pintype "passive"))
      (node (ref "MOTOR_DRIVER") (pin "8") (pinfunction "8_8") (pintype "passive"))
    )
    (net (code "42") (name "MISO") (class "Default")
      (node (ref "EYFI_MEGA") (pin "80") (pinfunction "MISO_PB3_80") (pintype "bidirectional"))
      (node (ref "SPI1") (pin "3") (pinfunction "3_3") (pintype "passive"))
    )
    (net (code "43") (name "MOSI") (class "Default")
      (node (ref "EYFI_MEGA") (pin "78") (pinfunction "MOSI_PB2_78") (pintype "bidirectional"))
      (node (ref "SPI1") (pin "5") (pinfunction "5_5") (pintype "passive"))
    )
    (net (code "44") (name "Net-(BUZZER-1)") (class "Default")
      (node (ref "BUZZER") (pin "+") (pinfunction "1_+") (pintype "passive"))
      (node (ref "BUZZ_TRN") (pin "E") (pinfunction "E_E") (pintype "passive"))
    )
    (net (code "45") (name "Net-(BUZZ_TRN-PadB)") (class "Default")
      (node (ref "BUZZ_TRN") (pin "B") (pinfunction "B_B") (pintype "passive"))
      (node (ref "R9") (pin "2") (pinfunction "2_2") (pintype "passive"))
    )
    (net (code "46") (name "Net-(D1-A)") (class "Default")
      (node (ref "D1") (pin "7") (pinfunction "A_7") (pintype "passive"))
      (node (ref "R1") (pin "2") (pinfunction "2_2") (pintype "passive"))
    )
    (net (code "47") (name "Net-(D1-B)") (class "Default")
      (node (ref "D1") (pin "6") (pinfunction "B_6") (pintype "passive"))
      (node (ref "R2") (pin "2") (pinfunction "2_2") (pintype "passive"))
    )
    (net (code "48") (name "Net-(D1-C)") (class "Default")
      (node (ref "D1") (pin "4") (pinfunction "C_4") (pintype "passive"))
      (node (ref "R3") (pin "2") (pinfunction "2_2") (pintype "passive"))
    )
    (net (code "49") (name "Net-(D1-CK1)") (class "Default")
      (node (ref "D1") (pin "3") (pinfunction "CK1_3") (pintype "passive"))
      (node (ref "D1") (pin "8") (pinfunction "CK2_8") (pintype "passive"))
      (node (ref "JP4") (pin "3") (pinfunction "3_3") (pintype "passive"))
    )
    (net (code "50") (name "Net-(D1-D)") (class "Default")
      (node (ref "D1") (pin "2") (pinfunction "D_2") (pintype "passive"))
      (node (ref "R4") (pin "2") (pinfunction "2_2") (pintype "passive"))
    )
    (net (code "51") (name "Net-(D1-DP)") (class "Default")
      (node (ref "D1") (pin "5") (pinfunction "DP_5") (pintype "passive"))
      (node (ref "R8") (pin "1") (pinfunction "1_1") (pintype "passive"))
    )
    (net (code "52") (name "Net-(D1-E)") (class "Default")
      (node (ref "D1") (pin "1") (pinfunction "E_1") (pintype "passive"))
      (node (ref "R5") (pin "2") (pinfunction "2_2") (pintype "passive"))
    )
    (net (code "53") (name "Net-(D1-F)") (class "Default")
      (node (ref "D1") (pin "9") (pinfunction "F_9") (pintype "passive"))
      (node (ref "R6") (pin "1") (pinfunction "1_1") (pintype "passive"))
    )
    (net (code "54") (name "Net-(D1-G)") (class "Default")
      (node (ref "D1") (pin "10") (pinfunction "G_10") (pintype "passive"))
      (node (ref "R7") (pin "1") (pinfunction "1_1") (pintype "passive"))
    )
    (net (code "55") (name "Net-(JP1-Pad1)") (class "Default")
      (node (ref "JP1") (pin "1") (pinfunction "1_1") (pintype "passive"))
      (node (ref "SHARP_1") (pin "1") (pinfunction "1_1") (pintype "passive"))
    )
    (net (code "56") (name "Net-(JP2-Pad1)") (class "Default")
      (node (ref "JP2") (pin "1") (pinfunction "1_1") (pintype "passive"))
      (node (ref "SERVO_1") (pin "3") (pinfunction "3_3") (pintype "passive"))
      (node (ref "SERVO_2") (pin "3") (pinfunction "3_3") (pintype "passive"))
      (node (ref "SERVO_3") (pin "3") (pinfunction "3_3") (pintype "passive"))
    )
    (net (code "57") (name "Net-(JP3-Pad3)") (class "Default")
      (node (ref "JP3") (pin "3") (pinfunction "3_3") (pintype "passive"))
      (node (ref "ULTRASONIC") (pin "1") (pinfunction "1_1") (pintype "passive"))
    )
    (net (code "58") (name "Net-(JP5-Pad3)") (class "Default")
      (node (ref "JP5") (pin "3") (pinfunction "3_3") (pintype "passive"))
      (node (ref "OLED_1") (pin "1") (pinfunction "1_1") (pintype "passive"))
      (node (ref "OLED_2") (pin "1") (pinfunction "1_1") (pintype "passive"))
    )
    (net (code "59") (name "Net-(JP6-Pad3)") (class "Default")
      (node (ref "JP6") (pin "3") (pinfunction "3_3") (pintype "passive"))
      (node (ref "OLED_1") (pin "2") (pinfunction "2_2") (pintype "passive"))
      (node (ref "OLED_2") (pin "2") (pinfunction "2_2") (pintype "passive"))
    )
    (net (code "60") (name "Net-(JP7-Pad1)") (class "Default")
      (node (ref "JP7") (pin "1") (pinfunction "1_1") (pintype "passive"))
      (node (ref "LINE_FOLLOWER_HEADER") (pin "1") (pinfunction "1_1") (pintype "passive"))
    )
    (net (code "61") (name "Net-(JP8-Pad1)") (class "Default")
      (node (ref "JP8") (pin "1") (pinfunction "1_1") (pintype "passive"))
      (node (ref "SHARP_2") (pin "1") (pinfunction "1_1") (pintype "passive"))
    )
    (net (code "62") (name "Net-(JP9-Pad1)") (class "Default")
      (node (ref "JP9") (pin "1") (pinfunction "1_1") (pintype "passive"))
      (node (ref "SHARP_3") (pin "1") (pinfunction "1_1") (pintype "passive"))
    )
    (net (code "63") (name "Net-(JP10-Pad1)") (class "Default")
      (node (ref "JP10") (pin "1") (pinfunction "1_1") (pintype "passive"))
      (node (ref "SHARP_4") (pin "1") (pinfunction "1_1") (pintype "passive"))
    )
    (net (code "64") (name "Net-(R11-Pad2)") (class "Default")
      (node (ref "R11") (pin "2") (pinfunction "2_2") (pintype "passive"))
      (node (ref "R12") (pin "1") (pinfunction "1_1") (pintype "passive"))
    )
    (net (code "65") (name "OC0A") (class "Default")
      (node (ref "EYFI_MEGA") (pin "47") (pinfunction "OC0A_47") (pintype "bidirectional"))
      (node (ref "PWM1_1") (pin "6") (pinfunction "6_6") (pintype "passive"))
    )
    (net (code "66") (name "OC0B") (class "Default")
      (node (ref "EYFI_MEGA") (pin "46") (pinfunction "OC0B_46") (pintype "bidirectional"))
      (node (ref "PWM1_1") (pin "7") (pinfunction "7_7") (pintype "passive"))
    )
    (net (code "67") (name "OC1A") (class "Default")
      (node (ref "EYFI_MEGA") (pin "44") (pinfunction "OC1A_44") (pintype "bidirectional"))
      (node (ref "PWM1_2") (pin "3") (pinfunction "3_3") (pintype "passive"))
    )
    (net (code "68") (name "OC1B") (class "Default")
      (node (ref "ARDU_CAM") (pin "7") (pinfunction "7_7") (pintype "passive"))
      (node (ref "EYFI_MEGA") (pin "45") (pinfunction "OC1B_45") (pintype "bidirectional"))
      (node (ref "PWM1_1") (pin "8") (pinfunction "8_8") (pintype "passive"))
    )
    (net (code "69") (name "OC2A") (class "Default")
      (node (ref "EYFI_MEGA") (pin "43") (pinfunction "OC2A_43") (pintype "bidirectional"))
      (node (ref "PWM1_2") (pin "4") (pinfunction "4_4") (pintype "passive"))
    )
    (net (code "70") (name "OC2B") (class "Default")
      (node (ref "EYFI_MEGA") (pin "42") (pinfunction "OC2B_42") (pintype "bidirectional"))
      (node (ref "PWM1_2") (pin "5") (pinfunction "5_5") (pintype "passive"))
      (node (ref "R10") (pin "2") (pinfunction "2_2") (pintype "passive"))
    )
    (net (code "71") (name "OC3A") (class "Default")
      (node (ref "EYFI_MEGA") (pin "38") (pinfunction "OC3A_38") (pintype "bidirectional"))
      (node (ref "PWM1_2") (pin "9") (pinfunction "9_9") (pintype "passive"))
      (node (ref "R9") (pin "1") (pinfunction "1_1") (pintype "passive"))
    )
    (net (code "72") (name "OC4A") (class "Default")
      (node (ref "EYFI_MEGA") (pin "39") (pinfunction "OC4A_39") (pintype "bidirectional"))
      (node (ref "PWM1_2") (pin "8") (pinfunction "8_8") (pintype "passive"))
      (node (ref "SERVO_1") (pin "2") (pinfunction "2_2") (pintype "passive"))
    )
    (net (code "73") (name "OC4B") (class "Default")
      (node (ref "EYFI_MEGA") (pin "40") (pinfunction "OC4B_40") (pintype "bidirectional"))
      (node (ref "PWM1_2") (pin "7") (pinfunction "7_7") (pintype "passive"))
      (node (ref "SERVO_2") (pin "2") (pinfunction "2_2") (pintype "passive"))
    )
    (net (code "74") (name "OC4C") (class "Default")
      (node (ref "EYFI_MEGA") (pin "41") (pinfunction "OC4C_41") (pintype "bidirectional"))
      (node (ref "PWM1_2") (pin "6") (pinfunction "6_6") (pintype "passive"))
      (node (ref "SERVO_3") (pin "2") (pinfunction "2_2") (pintype "passive"))
    )
    (net (code "75") (name "OC5A") (class "Default")
      (node (ref "EYFI_MEGA") (pin "48") (pinfunction "OC5A_48") (pintype "bidirectional"))
      (node (ref "MOTOR_DRIVER") (pin "5") (pinfunction "5_5") (pintype "passive"))
      (node (ref "PWM1_1") (pin "5") (pinfunction "5_5") (pintype "passive"))
    )
    (net (code "76") (name "OC5B") (class "Default")
      (node (ref "EYFI_MEGA") (pin "49") (pinfunction "OC5B_49") (pintype "bidirectional"))
      (node (ref "MOTOR_DRIVER") (pin "6") (pinfunction "6_6") (pintype "passive"))
      (node (ref "PWM1_1") (pin "4") (pinfunction "4_4") (pintype "passive"))
    )
    (net (code "77") (name "OC5C") (class "Default")
      (node (ref "EYFI_MEGA") (pin "50") (pinfunction "OC5C_50") (pintype "bidirectional"))
      (node (ref "PWM1_1") (pin "3") (pinfunction "3_3") (pintype "passive"))
    )
    (net (code "78") (name "PA0") (class "Default")
      (node (ref "ARDU_CAM") (pin "16") (pinfunction "16_16") (pintype "passive"))
      (node (ref "EYFI_MEGA") (pin "102") (pinfunction "PA0_102") (pintype "bidirectional"))
      (node (ref "GPIO3") (pin "3") (pinfunction "3_3") (pintype "passive"))
    )
    (net (code "79") (name "PA1") (class "Default")
      (node (ref "ARDU_CAM") (pin "15") (pinfunction "15_15") (pintype "passive"))
      (node (ref "EYFI_MEGA") (pin "101") (pinfunction "PA1_101") (pintype "bidirectional"))
      (node (ref "GPIO3") (pin "4") (pinfunction "4_4") (pintype "passive"))
    )
    (net (code "80") (name "PA2") (class "Default")
      (node (ref "ARDU_CAM") (pin "14") (pinfunction "14_14") (pintype "passive"))
      (node (ref "EYFI_MEGA") (pin "100") (pinfunction "PA2_100") (pintype "bidirectional"))
      (node (ref "GPIO3") (pin "5") (pinfunction "5_5") (pintype "passive"))
    )
    (net (code "81") (name "PA3") (class "Default")
      (node (ref "ARDU_CAM") (pin "13") (pinfunction "13_13") (pintype "passive"))
      (node (ref "EYFI_MEGA") (pin "99") (pinfunction "PA3_99") (pintype "bidirectional"))
      (node (ref "GPIO3") (pin "6") (pinfunction "6_6") (pintype "passive"))
    )
    (net (code "82") (name "PA4") (class "Default")
      (node (ref "ARDU_CAM") (pin "12") (pinfunction "12_12") (pintype "passive"))
      (node (ref "EYFI_MEGA") (pin "98") (pinfunction "PA4_98") (pintype "bidirectional"))
      (node (ref "GPIO3") (pin "7") (pinfunction "7_7") (pintype "passive"))
    )
    (net (code "83") (name "PA5") (class "Default")
      (node (ref "ARDU_CAM") (pin "11") (pinfunction "11_11") (pintype "passive"))
      (node (ref "EYFI_MEGA") (pin "97") (pinfunction "PA5_97") (pintype "bidirectional"))
      (node (ref "GPIO3") (pin "8") (pinfunction "8_8") (pintype "passive"))
    )
    (net (code "84") (name "PA6") (class "Default")
      (node (ref "ARDU_CAM") (pin "10") (pinfunction "10_10") (pintype "passive"))
      (node (ref "EYFI_MEGA") (pin "96") (pinfunction "PA6_96") (pintype "bidirectional"))
      (node (ref "GPIO3") (pin "9") (pinfunction "9_9") (pintype "passive"))
    )
    (net (code "85") (name "PA7") (class "Default")
      (node (ref "ARDU_CAM") (pin "9") (pinfunction "9_9") (pintype "passive"))
      (node (ref "EYFI_MEGA") (pin "95") (pinfunction "PA7_95") (pintype "bidirectional"))
      (node (ref "GPIO3") (pin "10") (pinfunction "10_10") (pintype "passive"))
    )
    (net (code "86") (name "PB1") (class "Default")
      (node (ref "EYFI_MEGA") (pin "75") (pinfunction "SCK_PB1_75") (pintype "bidirectional"))
      (node (ref "SPI1") (pin "8") (pinfunction "8_8") (pintype "passive"))
    )
    (net (code "87") (name "PB2") (class "Default")
      (node (ref "EYFI_MEGA") (pin "77") (pinfunction "MOSI_PB2_77") (pintype "bidirectional"))
      (node (ref "SPI1") (pin "6") (pinfunction "6_6") (pintype "passive"))
    )
    (net (code "88") (name "PB3") (class "Default")
      (node (ref "EYFI_MEGA") (pin "79") (pinfunction "MISO_PB3_79") (pintype "bidirectional"))
      (node (ref "SPI1") (pin "4") (pinfunction "4_4") (pintype "passive"))
    )
    (net (code "89") (name "PC0") (class "Default")
      (node (ref "EYFI_MEGA") (pin "6") (pinfunction "PC0_6") (pintype "bidirectional"))
      (node (ref "GPIO1") (pin "6") (pinfunction "6_6") (pintype "passive"))
      (node (ref "R1") (pin "1") (pinfunction "1_1") (pintype "passive"))
    )
    (net (code "90") (name "PC1") (class "Default")
      (node (ref "EYFI_MEGA") (pin "5") (pinfunction "PC1_5") (pintype "bidirectional"))
      (node (ref "GPIO1") (pin "5") (pinfunction "5_5") (pintype "passive"))
      (node (ref "R2") (pin "1") (pinfunction "1_1") (pintype "passive"))
    )
    (net (code "91") (name "PC2") (class "Default")
      (node (ref "EYFI_MEGA") (pin "4") (pinfunction "PC2_4") (pintype "bidirectional"))
      (node (ref "GPIO1") (pin "4") (pinfunction "4_4") (pintype "passive"))
      (node (ref "R3") (pin "1") (pinfunction "1_1") (pintype "passive"))
    )
    (net (code "92") (name "PC3") (class "Default")
      (node (ref "EYFI_MEGA") (pin "3") (pinfunction "PC3_3") (pintype "bidirectional"))
      (node (ref "GPIO1") (pin "3") (pinfunction "3_3") (pintype "passive"))
      (node (ref "R4") (pin "1") (pinfunction "1_1") (pintype "passive"))
    )
    (net (code "93") (name "PC4") (class "Default")
      (node (ref "EYFI_MEGA") (pin "85") (pinfunction "PC4_85") (pintype "bidirectional"))
      (node (ref "GPIO3") (pin "20") (pinfunction "20_20") (pintype "passive"))
      (node (ref "R5") (pin "1") (pinfunction "1_1") (pintype "passive"))
    )
    (net (code "94") (name "PC5") (class "Default")
      (node (ref "EYFI_MEGA") (pin "86") (pinfunction "PC5_86") (pintype "bidirectional"))
      (node (ref "GPIO3") (pin "19") (pinfunction "19_19") (pintype "passive"))
      (node (ref "R6") (pin "2") (pinfunction "2_2") (pintype "passive"))
    )
    (net (code "95") (name "PC6") (class "Default")
      (node (ref "EYFI_MEGA") (pin "87") (pinfunction "PC6_87") (pintype "bidirectional"))
      (node (ref "GPIO3") (pin "18") (pinfunction "18_18") (pintype "passive"))
      (node (ref "R7") (pin "2") (pinfunction "2_2") (pintype "passive"))
    )
    (net (code "96") (name "PC7") (class "Default")
      (node (ref "EYFI_MEGA") (pin "88") (pinfunction "PC7_88") (pintype "bidirectional"))
      (node (ref "GPIO3") (pin "17") (pinfunction "17_17") (pintype "passive"))
      (node (ref "R8") (pin "2") (pinfunction "2_2") (pintype "passive"))
    )
    (net (code "97") (name "PD0") (class "Default")
      (node (ref "EYFI_MEGA") (pin "107") (pinfunction "SCL_PD0_107") (pintype "bidirectional"))
      (node (ref "I2C1") (pin "6") (pinfunction "6_6") (pintype "passive"))
    )
    (net (code "98") (name "PD1") (class "Default")
      (node (ref "EYFI_MEGA") (pin "109") (pinfunction "SDA_PD1_109") (pintype "bidirectional"))
      (node (ref "I2C1") (pin "4") (pinfunction "4_4") (pintype "passive"))
    )
    (net (code "99") (name "PD4") (class "Default")
      (node (ref "EYFI_MEGA") (pin "12") (pinfunction "PD4_12") (pintype "bidirectional"))
      (node (ref "GPIO1") (pin "12") (pinfunction "12_12") (pintype "passive"))
      (node (ref "MOTOR_DRIVER") (pin "1") (pinfunction "1_1") (pintype "passive"))
    )
    (net (code "100") (name "PD5") (class "Default")
      (node (ref "EYFI_MEGA") (pin "11") (pinfunction "PD5_11") (pintype "bidirectional"))
      (node (ref "GPIO1") (pin "11") (pinfunction "11_11") (pintype "passive"))
      (node (ref "MOTOR_DRIVER") (pin "2") (pinfunction "2_2") (pintype "passive"))
    )
    (net (code "101") (name "PD6") (class "Default")
      (node (ref "EYFI_MEGA") (pin "10") (pinfunction "PD6_10") (pintype "bidirectional"))
      (node (ref "GPIO1") (pin "10") (pinfunction "10_10") (pintype "passive"))
      (node (ref "MOTOR_DRIVER") (pin "3") (pinfunction "3_3") (pintype "passive"))
    )
    (net (code "102") (name "PD7") (class "Default")
      (node (ref "EYFI_MEGA") (pin "9") (pinfunction "PD7_9") (pintype "bidirectional"))
      (node (ref "GPIO1") (pin "9") (pinfunction "9_9") (pintype "passive"))
      (node (ref "MOTOR_DRIVER") (pin "4") (pinfunction "4_4") (pintype "passive"))
    )
    (net (code "103") (name "PE2") (class "Default")
      (node (ref "EYFI_MEGA") (pin "20") (pinfunction "PE2_20") (pintype "bidirectional"))
      (node (ref "GPIO1") (pin "20") (pinfunction "20_20") (pintype "passive"))
    )
    (net (code "104") (name "PG0") (class "Default")
      (node (ref "EYFI_MEGA") (pin "8") (pinfunction "PG0_8") (pintype "bidirectional"))
      (node (ref "GPIO1") (pin "8") (pinfunction "8_8") (pintype "passive"))
    )
    (net (code "105") (name "PG1") (class "Default")
      (node (ref "EYFI_MEGA") (pin "7") (pinfunction "PG1_7") (pintype "bidirectional"))
      (node (ref "GPIO1") (pin "7") (pinfunction "7_7") (pintype "passive"))
    )
    (net (code "106") (name "PG2") (class "Default")
      (node (ref "EYFI_MEGA") (pin "94") (pinfunction "PG2_94") (pintype "bidirectional"))
      (node (ref "GPIO3") (pin "11") (pinfunction "11_11") (pintype "passive"))
      (node (ref "ULTRASONIC") (pin "2") (pinfunction "2_2") (pintype "passive"))
    )
    (net (code "107") (name "PH2") (class "Default")
      (node (ref "EYFI_MEGA") (pin "19") (pinfunction "PH2_19") (pintype "bidirectional"))
      (node (ref "GPIO1") (pin "19") (pinfunction "19_19") (pintype "passive"))
    )
    (net (code "108") (name "PH7") (class "Default")
      (node (ref "EYFI_MEGA") (pin "18") (pinfunction "PH7_18") (pintype "bidirectional"))
      (node (ref "GPIO1") (pin "18") (pinfunction "18_18") (pintype "passive"))
    )
    (net (code "109") (name "PJ2") (class "Default")
      (node (ref "EYFI_MEGA") (pin "89") (pinfunction "PJ2_89") (pintype "bidirectional"))
      (node (ref "GPIO3") (pin "16") (pinfunction "16_16") (pintype "passive"))
    )
    (net (code "110") (name "PJ3") (class "Default")
      (node (ref "EYFI_MEGA") (pin "90") (pinfunction "PJ3_90") (pintype "bidirectional"))
      (node (ref "GPIO3") (pin "15") (pinfunction "15_15") (pintype "passive"))
    )
    (net (code "111") (name "PJ4") (class "Default")
      (node (ref "EYFI_MEGA") (pin "91") (pinfunction "PJ4_91") (pintype "bidirectional"))
      (node (ref "GPIO3") (pin "14") (pinfunction "14_14") (pintype "passive"))
    )
    (net (code "112") (name "PJ5") (class "Default")
      (node (ref "EYFI_MEGA") (pin "92") (pinfunction "PJ5_92") (pintype "bidirectional"))
      (node (ref "GPIO3") (pin "13") (pinfunction "13_13") (pintype "passive"))
    )
    (net (code "113") (name "PJ6") (class "Default")
      (node (ref "EYFI_MEGA") (pin "93") (pinfunction "PJ6_93") (pintype "bidirectional"))
      (node (ref "GPIO3") (pin "12") (pinfunction "12_12") (pintype "passive"))
      (node (ref "ULTRASONIC") (pin "3") (pinfunction "3_3") (pintype "passive"))
    )
    (net (code "114") (name "PL0") (class "Default")
      (node (ref "EYFI_MEGA") (pin "17") (pinfunction "PL0_17") (pintype "bidirectional"))
      (node (ref "GPIO1") (pin "17") (pinfunction "17_17") (pintype "passive"))
    )
    (net (code "115") (name "PL1") (class "Default")
      (node (ref "EYFI_MEGA") (pin "16") (pinfunction "PL1_16") (pintype "bidirectional"))
      (node (ref "GPIO1") (pin "16") (pinfunction "16_16") (pintype "passive"))
    )
    (net (code "116") (name "PL2") (class "Default")
      (node (ref "EYFI_MEGA") (pin "15") (pinfunction "PL2_15") (pintype "bidirectional"))
      (node (ref "GPIO1") (pin "15") (pinfunction "15_15") (pintype "passive"))
    )
    (net (code "117") (name "PL6") (class "Default")
      (node (ref "EYFI_MEGA") (pin "14") (pinfunction "PL6_14") (pintype "bidirectional"))
      (node (ref "GPIO1") (pin "14") (pinfunction "14_14") (pintype "passive"))
    )
    (net (code "118") (name "PL7") (class "Default")
      (node (ref "EYFI_MEGA") (pin "13") (pinfunction "PL7_13") (pintype "bidirectional"))
      (node (ref "GPIO1") (pin "13") (pinfunction "13_13") (pintype "passive"))
    )
    (net (code "119") (name "RST") (class "Default")
      (node (ref "EYFI_MEGA") (pin "37") (pinfunction "RESET_37") (pintype "bidirectional"))
      (node (ref "PWM1_2") (pin "10") (pinfunction "10_10") (pintype "passive"))
    )
    (net (code "120") (name "RX1") (class "Default")
      (node (ref "ARDU_CAM") (pin "5") (pinfunction "5_5") (pintype "passive"))
      (node (ref "EYFI_MEGA") (pin "29") (pinfunction "RX1_29") (pintype "bidirectional"))
      (node (ref "UART1") (pin "7") (pinfunction "7_7") (pintype "passive"))
    )
    (net (code "121") (name "RX2") (class "Default")
      (node (ref "EYFI_MEGA") (pin "27") (pinfunction "RX2_27") (pintype "bidirectional"))
      (node (ref "UART1") (pin "5") (pinfunction "5_5") (pintype "passive"))
    )
    (net (code "122") (name "RX3") (class "Default")
      (node (ref "EYFI_MEGA") (pin "25") (pinfunction "RX3_25") (pintype "bidirectional"))
      (node (ref "UART1") (pin "3") (pinfunction "3_3") (pintype "passive"))
    )
    (net (code "123") (name "SCK") (class "Default")
      (node (ref "EYFI_MEGA") (pin "76") (pinfunction "SCK_PB1_76") (pintype "bidirectional"))
      (node (ref "SPI1") (pin "7") (pinfunction "7_7") (pintype "passive"))
    )
    (net (code "124") (name "SCL") (class "Default")
      (node (ref "ARDU_CAM") (pin "3") (pinfunction "3_3") (pintype "passive"))
      (node (ref "EYFI_MEGA") (pin "108") (pinfunction "SCL_PD0_108") (pintype "bidirectional"))
      (node (ref "I2C1") (pin "5") (pinfunction "5_5") (pintype "passive"))
      (node (ref "I2C_HEADER_1") (pin "3") (pinfunction "3_3") (pintype "passive"))
      (node (ref "I2C_HEADER_2") (pin "3") (pinfunction "3_3") (pintype "passive"))
      (node (ref "LINE_FOLLOWER_HEADER") (pin "3") (pinfunction "3_3") (pintype "passive"))
      (node (ref "OLED_1") (pin "3") (pinfunction "3_3") (pintype "passive"))
      (node (ref "OLED_2") (pin "3") (pinfunction "3_3") (pintype "passive"))
    )
    (net (code "125") (name "SDA") (class "Default")
      (node (ref "ARDU_CAM") (pin "4") (pinfunction "4_4") (pintype "passive"))
      (node (ref "EYFI_MEGA") (pin "110") (pinfunction "SDA_PD1_110") (pintype "bidirectional"))
      (node (ref "I2C1") (pin "3") (pinfunction "3_3") (pintype "passive"))
      (node (ref "I2C_HEADER_1") (pin "2") (pinfunction "2_2") (pintype "passive"))
      (node (ref "I2C_HEADER_2") (pin "2") (pinfunction "2_2") (pintype "passive"))
      (node (ref "LINE_FOLLOWER_HEADER") (pin "2") (pinfunction "2_2") (pintype "passive"))
      (node (ref "OLED_1") (pin "4") (pinfunction "4_4") (pintype "passive"))
      (node (ref "OLED_2") (pin "4") (pinfunction "4_4") (pintype "passive"))
    )
    (net (code "126") (name "SS0{slash}PB0") (class "Default")
      (node (ref "EYFI_MEGA") (pin "73") (pinfunction "SS0_PB0_73") (pintype "bidirectional"))
      (node (ref "SPI1") (pin "10") (pinfunction "10_10") (pintype "passive"))
    )
    (net (code "127") (name "SS1{slash}PJ7") (class "Default")
      (node (ref "EYFI_MEGA") (pin "74") (pinfunction "SS1_PJ7_74") (pintype "bidirectional"))
      (node (ref "SPI1") (pin "9") (pinfunction "9_9") (pintype "passive"))
    )
    (net (code "128") (name "TX1") (class "Default")
      (node (ref "EYFI_MEGA") (pin "30") (pinfunction "TX1_30") (pintype "bidirectional"))
      (node (ref "UART1") (pin "8") (pinfunction "8_8") (pintype "passive"))
    )
    (net (code "129") (name "TX2") (class "Default")
      (node (ref "EYFI_MEGA") (pin "28") (pinfunction "TX2_28") (pintype "bidirectional"))
      (node (ref "UART1") (pin "6") (pinfunction "6_6") (pintype "passive"))
    )
    (net (code "130") (name "TX3") (class "Default")
      (node (ref "EYFI_MEGA") (pin "26") (pinfunction "TX3_26") (pintype "bidirectional"))
      (node (ref "UART1") (pin "4") (pinfunction "4_4") (pintype "passive"))
    )
    (net (code "131") (name "XCLK") (class "Default")
      (node (ref "ARDU_CAM") (pin "8") (pinfunction "8_8") (pintype "passive"))
      (node (ref "R10") (pin "1") (pinfunction "1_1") (pintype "passive"))
      (node (ref "R11") (pin "1") (pinfunction "1_1") (pintype "passive"))
    )
    (net (code "132") (name "unconnected-(ARDU_CAM-Pad6)") (class "Default")
      (node (ref "ARDU_CAM") (pin "6") (pinfunction "6_6") (pintype "passive"))
    )
    (net (code "133") (name "unconnected-(GY-87-Pad2)") (class "Default")
      (node (ref "GY-87") (pin "2") (pinfunction "2_2") (pintype "passive"))
    )
    (net (code "134") (name "unconnected-(GY-87-Pad4)") (class "Default")
      (node (ref "GY-87") (pin "4") (pinfunction "4_4") (pintype "passive"))
    )
    (net (code "135") (name "unconnected-(GY-87-Pad5)") (class "Default")
      (node (ref "GY-87") (pin "5") (pinfunction "5_5") (pintype "passive"))
    )
    (net (code "136") (name "unconnected-(GY-87-Pad6)") (class "Default")
      (node (ref "GY-87") (pin "6") (pinfunction "6_6") (pintype "passive"))
    )
    (net (code "137") (name "unconnected-(GY-87-Pad7)") (class "Default")
      (node (ref "GY-87") (pin "7") (pinfunction "7_7") (pintype "passive"))
    )
    (net (code "138") (name "unconnected-(GY-87-Pad8)") (class "Default")
      (node (ref "GY-87") (pin "8") (pinfunction "8_8") (pintype "passive"))
    )
    (net (code "139") (name "unconnected-(UART1-Pad9)") (class "Default")
      (node (ref "UART1") (pin "9") (pinfunction "9_9") (pintype "passive"))
    )
    (net (code "140") (name "unconnected-(UART1-Pad10)") (class "Default")
      (node (ref "UART1") (pin "10") (pinfunction "10_10") (pintype "passive"))
    )
  )
)
